# main.net
KiCad netlist of a schematic drawn in Altium Designer
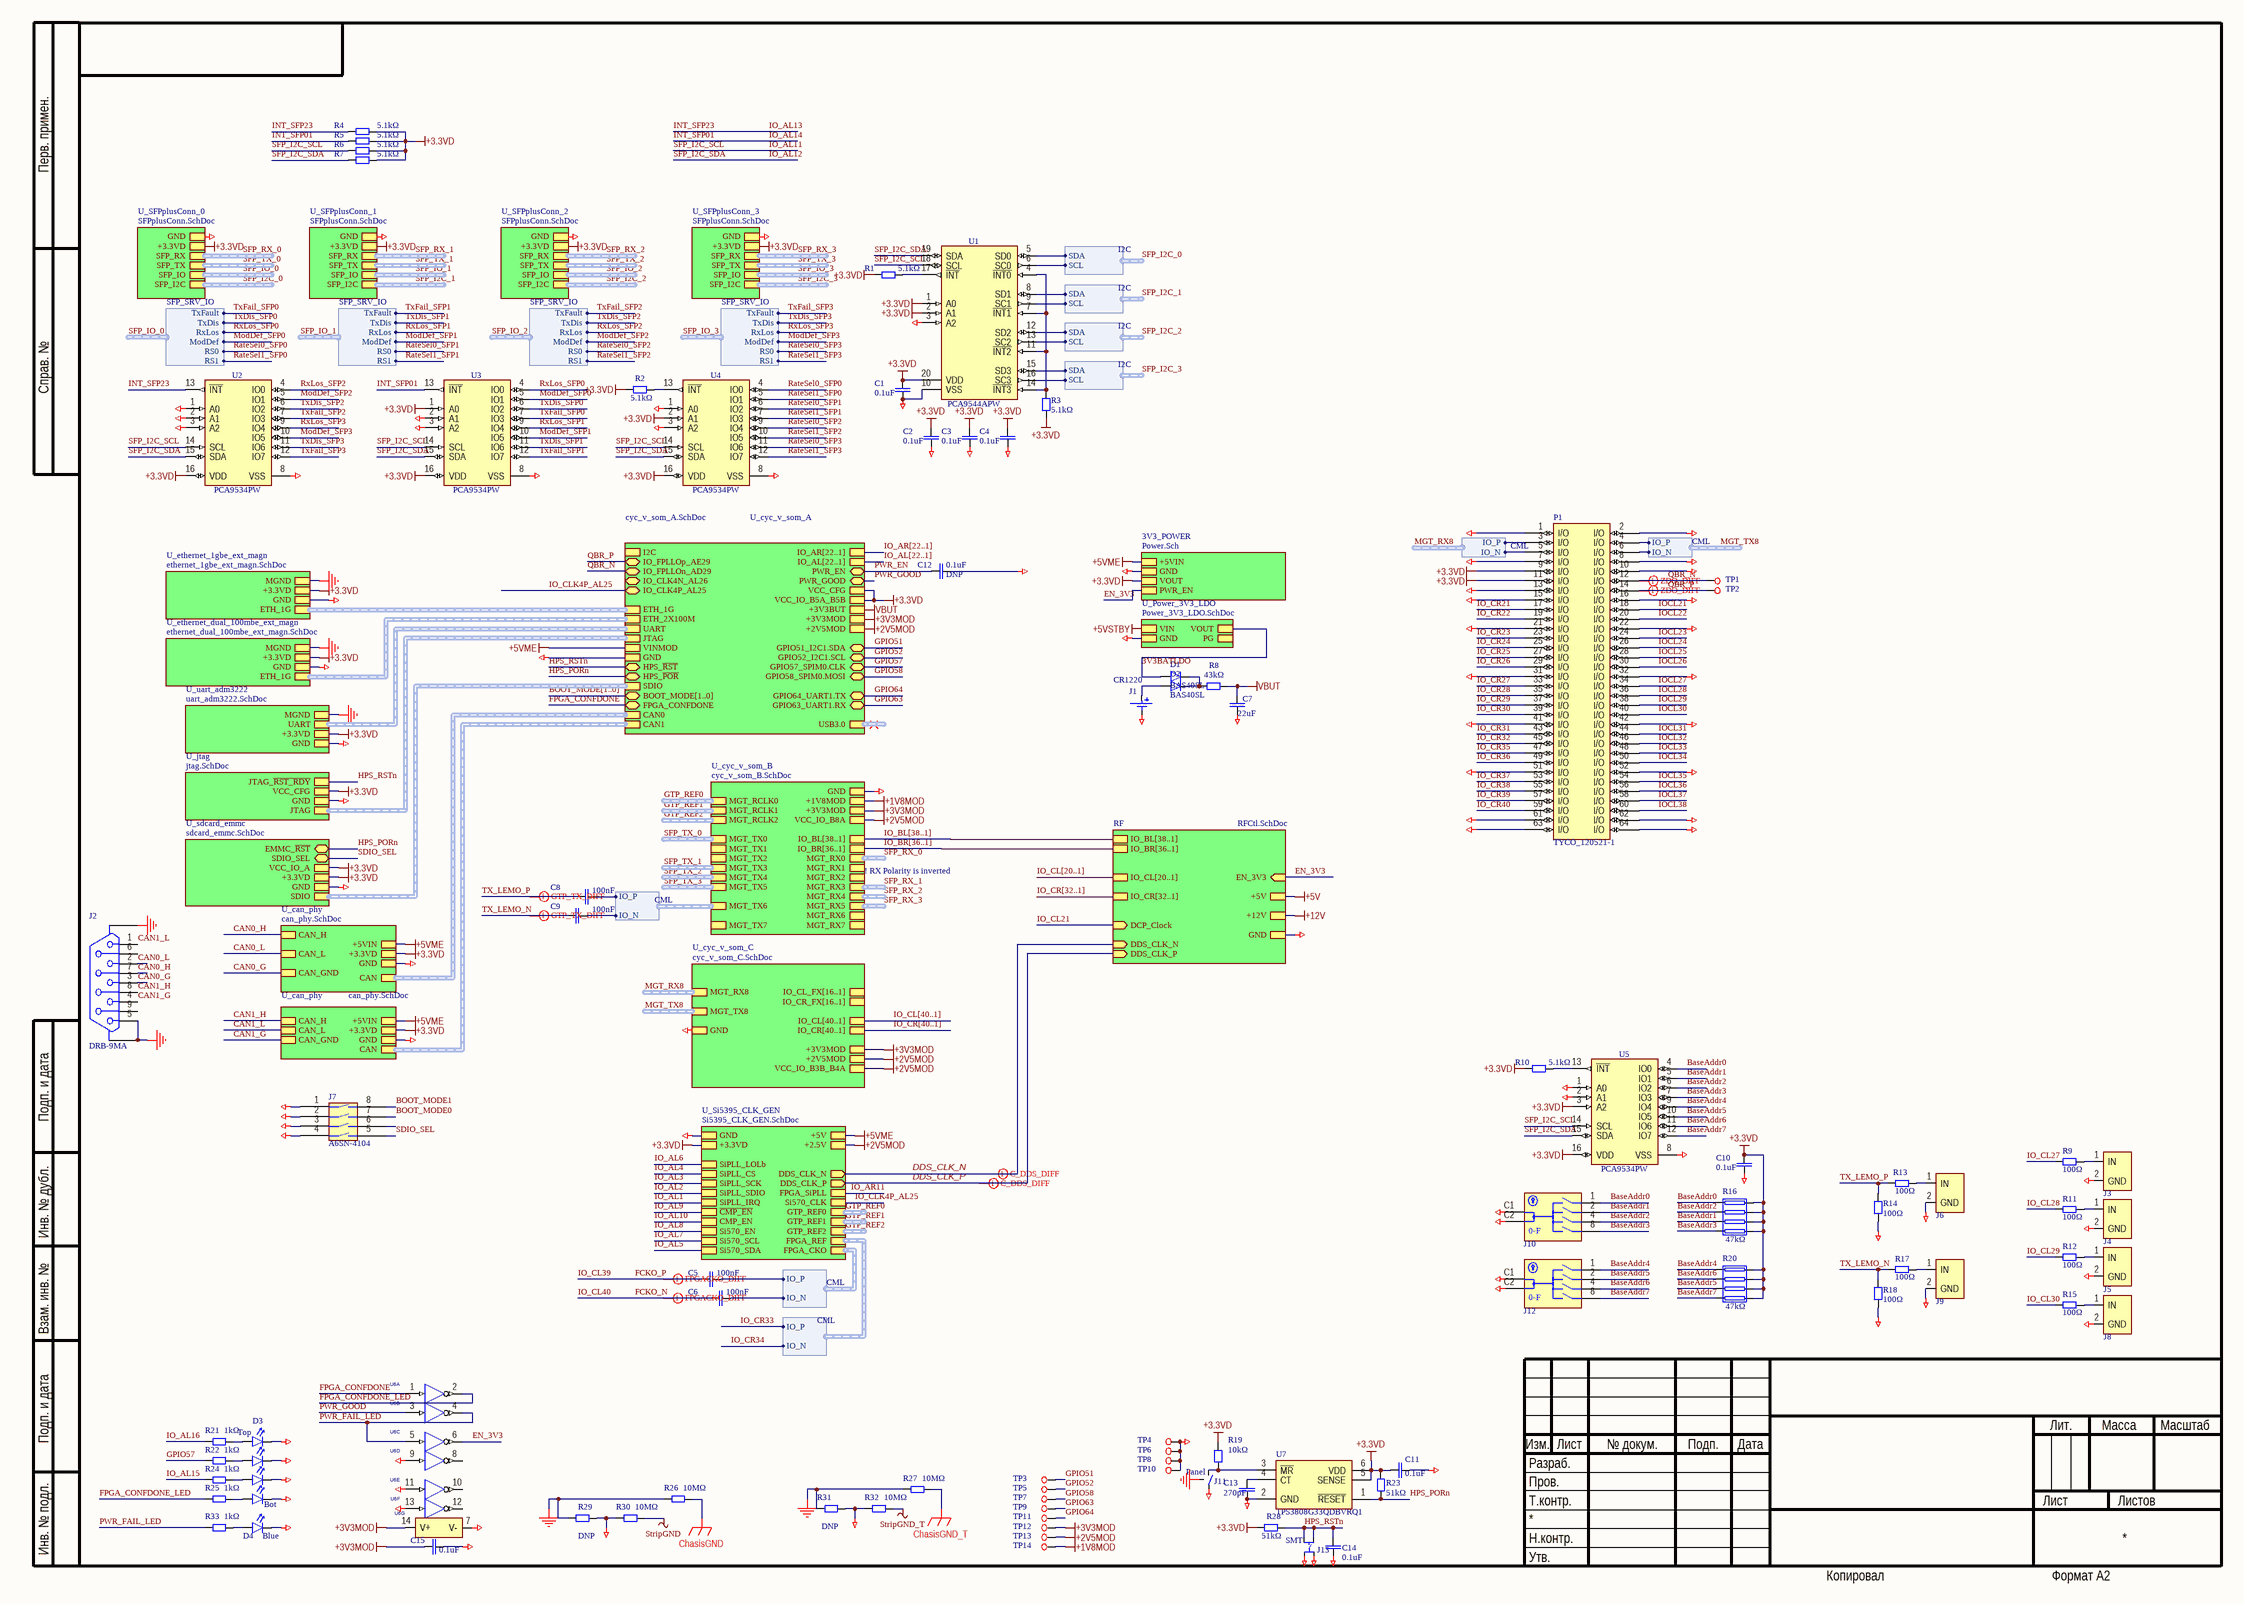
[diagram p0: main.SchDoc]

(export (version "E")
  (design (tool "Eeschema 10.0.6"))
  (components
    (comp (ref "C1")
      (value "0.1uF")
      (footprint "CAPC2012N")
      (description "Generic ceramic SMD capacitor")
      (fields (field (name "MAINTAINER") "Evgeniy Kotov"))
      (libsource (lib "[Capacitors] Capacitors SMD") (part "CAPC"))
    )
    (comp (ref "C2")
      (value "0.1uF")
      (footprint "CAPC2012N")
      (description "Generic ceramic SMD capacitor")
      (fields (field (name "MAINTAINER") "Evgeniy Kotov"))
      (libsource (lib "[Capacitors] Capacitors SMD") (part "CAPC"))
    )
    (comp (ref "C3")
      (value "0.1uF")
      (footprint "CAPC2012N")
      (description "Generic ceramic SMD capacitor")
      (fields (field (name "MAINTAINER") "Evgeniy Kotov"))
      (libsource (lib "[Capacitors] Capacitors SMD") (part "CAPC"))
    )
    (comp (ref "C4")
      (value "0.1uF")
      (footprint "CAPC2012N")
      (description "Generic ceramic SMD capacitor")
      (fields (field (name "MAINTAINER") "Evgeniy Kotov"))
      (libsource (lib "[Capacitors] Capacitors SMD") (part "CAPC"))
    )
    (comp (ref "C5")
      (value "100nF")
      (footprint "CAPC1608N")
      (description "Generic ceramic SMD capacitor")
      (fields (field (name "MAINTAINER") "Evgeniy Kotov"))
      (libsource (lib "carrier") (part "CAPC"))
    )
    (comp (ref "C6")
      (value "100nF")
      (footprint "CAPC1608N")
      (description "Generic ceramic SMD capacitor")
      (fields (field (name "MAINTAINER") "Evgeniy Kotov"))
      (libsource (lib "carrier") (part "CAPC"))
    )
    (comp (ref "C7")
      (value "22uF")
      (footprint "CAPC2012N")
      (description "Generic ceramic SMD capacitor")
      (fields (field (name "MAINTAINER") "Evgeniy Kotov"))
      (libsource (lib "carrier") (part "CAPC"))
    )
    (comp (ref "C8")
      (value "100nF")
      (footprint "CAPC1608N")
      (description "Generic ceramic SMD capacitor")
      (fields (field (name "MAINTAINER") "Evgeniy Kotov"))
      (libsource (lib "carrier") (part "CAPC"))
    )
    (comp (ref "C9")
      (value "100nF")
      (footprint "CAPC1608N")
      (description "Generic ceramic SMD capacitor")
      (fields (field (name "MAINTAINER") "Evgeniy Kotov"))
      (libsource (lib "carrier") (part "CAPC"))
    )
    (comp (ref "C10")
      (value "0.1uF")
      (footprint "CAPC2012N")
      (description "Generic ceramic SMD capacitor")
      (fields (field (name "MAINTAINER") "Evgeniy Kotov"))
      (libsource (lib "[Capacitors] Capacitors SMD") (part "CAPC"))
    )
    (comp (ref "C11")
      (value "0.1uF")
      (footprint "CAPC2012N")
      (description "Generic ceramic SMD capacitor")
      (fields (field (name "MAINTAINER") "Evgeniy Kotov"))
      (libsource (lib "[Capacitors] Capacitors SMD") (part "CAPC"))
    )
    (comp (ref "C12")
      (value "DNP")
      (footprint "CAPC2012N")
      (description "Generic ceramic SMD capacitor")
      (fields (field (name "PARTFIELD") "0.1uF") (field (name "MAINTAINER") "Evgeniy Kotov"))
      (libsource (lib "[Capacitors] Capacitors SMD") (part "CAPC"))
    )
    (comp (ref "C13")
      (value "270pF")
      (footprint "CAPC2012N")
      (description "Generic ceramic SMD capacitor")
      (fields (field (name "MAINTAINER") "Evgeniy Kotov"))
      (libsource (lib "[Capacitors] Capacitors SMD") (part "CAPC"))
    )
    (comp (ref "C14")
      (value "0.1uF")
      (footprint "CAPC2012N")
      (description "Generic ceramic SMD capacitor")
      (fields (field (name "MAINTAINER") "Evgeniy Kotov"))
      (libsource (lib "[Capacitors] Capacitors SMD") (part "CAPC"))
    )
    (comp (ref "C15")
      (value "0.1uF")
      (footprint "CAPC2012N")
      (description "Generic ceramic SMD capacitor")
      (fields (field (name "MAINTAINER") "Evgeniy Kotov"))
      (libsource (lib "[Capacitors] Capacitors SMD") (part "CAPC"))
    )
    (comp (ref "D1")
      (value "BAS40SL")
      (footprint "SOD_923")
      (description "Schottky Barrier Diode")
      (fields (field (name "MAINTAINER") "Evgeniy Kotov"))
      (libsource (lib "vme6U_carrier_Cyc_V_SoC") (part "BAS40SL"))
    )
    (comp (ref "D2")
      (value "BAS40SL")
      (footprint "SOD_923")
      (description "Schottky Barrier Diode")
      (fields (field (name "MAINTAINER") "Evgeniy Kotov"))
      (libsource (lib "vme6U_carrier_Cyc_V_SoC") (part "BAS40SL"))
    )
    (comp (ref "D3")
      (value "H485CGDL")
      (footprint "LED_H485C")
      (fields (field (name "MAINTAINER") "Evgeniy Kotov"))
      (libsource (lib "[ICs And Semiconductors] Diodes") (part "LEDx4_H485CGDL"))
    )
    (comp (ref "D4")
      (value "LB Q39E-N1OO-35-1")
      (footprint "LEDC1608N")
      (description "SMD Led, 0603")
      (fields (field (name "COLOR") "Blue") (field (name "MAINTAINER") "Evgeniy Kotov"))
      (libsource (lib "[ICs And Semiconductors] Diodes") (part "LED_SMD0603"))
    )
    (comp (ref "J1")
      (value "BC501SM")
      (footprint "BAT_CR1220")
      (description "BATTERY HOLDER COIN 12.5MM SMD")
      (fields (field (name "MAINTAINER") "Evgeniy Kotov"))
      (libsource (lib "[Connectors] Miscellaneous") (part "BAT_CR1220"))
    )
    (comp (ref "J2")
      (value "DRB-9MA")
      (footprint "DRB-9MA")
      (description "D-SUB; 9-pin, male, flange 7.2mm")
      (libsource (lib "[Connectors] Miscellaneous") (part "DRB-9MA"))
    )
    (comp (ref "J3")
      (value "DNP")
      (footprint "LEMO_EPA.00.250.NTN")
      (libsource (lib "carrier") (part "LEMO_EPA.00.250"))
    )
    (comp (ref "J4")
      (value "DNP")
      (footprint "LEMO_EPA.00.250.NTN")
      (libsource (lib "carrier") (part "LEMO_EPA.00.250"))
    )
    (comp (ref "J5")
      (value "DNP")
      (footprint "LEMO_EPA.00.250.NTN")
      (libsource (lib "carrier") (part "LEMO_EPA.00.250"))
    )
    (comp (ref "J6")
      (value "DNP")
      (footprint "LEMO_EPA.00.250.NTN")
      (libsource (lib "carrier") (part "LEMO_EPA.00.250"))
    )
    (comp (ref "J7")
      (value "A6SN-4104")
      (footprint "DIPSW4-A6SN8")
      (description "SMD DIP Switch, Omron A6H or A6SN series")
      (fields (field (name "MANUFACTURER") "Omron"))
      (libsource (lib "[Connectors] Miscellaneous") (part "DIPSW4"))
    )
    (comp (ref "J8")
      (value "DNP")
      (footprint "LEMO_EPA.00.250.NTN")
      (libsource (lib "carrier") (part "LEMO_EPA.00.250"))
    )
    (comp (ref "J9")
      (value "DNP")
      (footprint "LEMO_EPA.00.250.NTN")
      (libsource (lib "carrier") (part "LEMO_EPA.00.250"))
    )
    (comp (ref "J10")
      (value "ERD116XSZ")
      (footprint "SW_ECE_ERD116XSZ")
      (libsource (lib "[Connectors] Miscellaneous") (part "ERD116XSZ"))
    )
    (comp (ref "J11")
      (value "PTS645VL582LFS")
      (footprint "PTS645VL582LFS")
      (description "Tactile Switch SPST-NO Side Actuated Through Hole, Right Angle")
      (fields (field (name "MAINTAINER") "Evgeniy Kotov"))
      (libsource (lib "[Connectors] Miscellaneous") (part "PTS645VL582LFS"))
    )
    (comp (ref "J12")
      (value "ERD116XSZ")
      (footprint "SW_ECE_ERD116XSZ")
      (libsource (lib "[Connectors] Miscellaneous") (part "ERD116XSZ"))
    )
    (comp (ref "J13")
      (value "PTS645SL43SMTR92")
      (footprint "PTS645SL43SMTR92")
      (description "Tactile Switch SPST-NO Top Actuated Surface Mount")
      (fields (field (name "MAINTAINER") "Evgeniy Kotov"))
      (libsource (lib "[Connectors] Miscellaneous") (part "PTS645SL43SMTR92"))
    )
    (comp (ref "P1")
      (value "TYCO_120521-1")
      (footprint "TYCO_120521-1")
      (description "PCI Mezzanine Connector; IEEE 1386")
      (fields (field (name "MANUFACTURER") "TE Connectivity"))
      (libsource (lib "[Connectors] Miscellaneous") (part "PCI_PMC_TYCO_120521-1"))
    )
    (comp (ref "R1")
      (value "5.1kΩ")
      (footprint "RESC2012N")
      (description "Resistor, Generic, SMD")
      (fields (field (name "MAINTAINER") "Evgeniy Kotov"))
      (libsource (lib "carrier") (part "RESC"))
    )
    (comp (ref "R2")
      (value "5.1kΩ")
      (footprint "RESC2012N")
      (description "Resistor, Generic, SMD")
      (fields (field (name "MAINTAINER") "Evgeniy Kotov"))
      (libsource (lib "carrier") (part "RESC"))
    )
    (comp (ref "R3")
      (value "5.1kΩ")
      (footprint "RESC2012N")
      (description "Resistor, Generic, SMD")
      (fields (field (name "MAINTAINER") "Evgeniy Kotov"))
      (libsource (lib "[Resistors] Resistors SMD") (part "RESC"))
    )
    (comp (ref "R4")
      (value "5.1kΩ")
      (footprint "RESC2012N")
      (description "Resistor, Generic, SMD")
      (fields (field (name "MAINTAINER") "Evgeniy Kotov"))
      (libsource (lib "[Resistors] Resistors SMD") (part "RESC"))
    )
    (comp (ref "R5")
      (value "5.1kΩ")
      (footprint "RESC2012N")
      (description "Resistor, Generic, SMD")
      (fields (field (name "MAINTAINER") "Evgeniy Kotov"))
      (libsource (lib "[Resistors] Resistors SMD") (part "RESC"))
    )
    (comp (ref "R6")
      (value "5.1kΩ")
      (footprint "RESC2012N")
      (description "Resistor, Generic, SMD")
      (fields (field (name "MAINTAINER") "Evgeniy Kotov"))
      (libsource (lib "[Resistors] Resistors SMD") (part "RESC"))
    )
    (comp (ref "R7")
      (value "5.1kΩ")
      (footprint "RESC2012N")
      (description "Resistor, Generic, SMD")
      (fields (field (name "MAINTAINER") "Evgeniy Kotov"))
      (libsource (lib "[Resistors] Resistors SMD") (part "RESC"))
    )
    (comp (ref "R8")
      (value "43kΩ")
      (footprint "RESC2012N")
      (description "Resistor, Generic, SMD")
      (fields (field (name "MAINTAINER") "Evgeniy Kotov"))
      (libsource (lib "[Resistors] Resistors SMD") (part "RESC"))
    )
    (comp (ref "R9")
      (value "100Ω")
      (footprint "RESC1608N")
      (description "Resistor, Generic, SMD")
      (fields (field (name "MAINTAINER") "Evgeniy Kotov"))
      (libsource (lib "carrier") (part "RESC"))
    )
    (comp (ref "R10")
      (value "5.1kΩ")
      (footprint "RESC2012N")
      (description "Resistor, Generic, SMD")
      (fields (field (name "MAINTAINER") "Evgeniy Kotov"))
      (libsource (lib "carrier") (part "RESC"))
    )
    (comp (ref "R11")
      (value "100Ω")
      (footprint "RESC1608N")
      (description "Resistor, Generic, SMD")
      (fields (field (name "MAINTAINER") "Evgeniy Kotov"))
      (libsource (lib "carrier") (part "RESC"))
    )
    (comp (ref "R12")
      (value "100Ω")
      (footprint "RESC1608N")
      (description "Resistor, Generic, SMD")
      (fields (field (name "MAINTAINER") "Evgeniy Kotov"))
      (libsource (lib "carrier") (part "RESC"))
    )
    (comp (ref "R13")
      (value "100Ω")
      (footprint "RESC1608N")
      (description "Resistor, Generic, SMD")
      (fields (field (name "MAINTAINER") "Evgeniy Kotov"))
      (libsource (lib "carrier") (part "RESC"))
    )
    (comp (ref "R14")
      (value "100Ω")
      (footprint "RESC1608N")
      (description "Resistor, Generic, SMD")
      (fields (field (name "MAINTAINER") "Evgeniy Kotov"))
      (libsource (lib "carrier") (part "RESC"))
    )
    (comp (ref "R15")
      (value "100Ω")
      (footprint "RESC1608N")
      (description "Resistor, Generic, SMD")
      (fields (field (name "MAINTAINER") "Evgeniy Kotov"))
      (libsource (lib "carrier") (part "RESC"))
    )
    (comp (ref "R16")
      (value "47kΩ")
      (footprint "CAY16-J4")
      (fields (field (name "Comment") "CAY16-4702F4LF") (field (name "MAINTAINER") "Anton Pavlenko"))
      (libsource (lib "[Resistors] Resistors SMD") (part "RESPACK4"))
    )
    (comp (ref "R17")
      (value "100Ω")
      (footprint "RESC1608N")
      (description "Resistor, Generic, SMD")
      (fields (field (name "MAINTAINER") "Evgeniy Kotov"))
      (libsource (lib "carrier") (part "RESC"))
    )
    (comp (ref "R18")
      (value "100Ω")
      (footprint "RESC1608N")
      (description "Resistor, Generic, SMD")
      (fields (field (name "MAINTAINER") "Evgeniy Kotov"))
      (libsource (lib "carrier") (part "RESC"))
    )
    (comp (ref "R19")
      (value "10kΩ")
      (footprint "RESC2012N")
      (description "Resistor, Generic, SMD")
      (fields (field (name "MAINTAINER") "Evgeniy Kotov"))
      (libsource (lib "carrier") (part "RESC"))
    )
    (comp (ref "R20")
      (value "47kΩ")
      (footprint "CAY16-J4")
      (fields (field (name "Comment") "CAY16-4702F4LF") (field (name "MAINTAINER") "Anton Pavlenko"))
      (libsource (lib "[Resistors] Resistors SMD") (part "RESPACK4"))
    )
    (comp (ref "R21")
      (value "1kΩ")
      (footprint "RESC2012N")
      (description "Resistor, Generic, SMD")
      (fields (field (name "MAINTAINER") "Evgeniy Kotov"))
      (libsource (lib "[Resistors] Resistors SMD") (part "RESC"))
    )
    (comp (ref "R22")
      (value "1kΩ")
      (footprint "RESC2012N")
      (description "Resistor, Generic, SMD")
      (fields (field (name "MAINTAINER") "Evgeniy Kotov"))
      (libsource (lib "[Resistors] Resistors SMD") (part "RESC"))
    )
    (comp (ref "R23")
      (value "51kΩ")
      (footprint "RESC2012N")
      (description "Resistor, Generic, SMD")
      (fields (field (name "MAINTAINER") "Evgeniy Kotov"))
      (libsource (lib "carrier") (part "RESC"))
    )
    (comp (ref "R24")
      (value "1kΩ")
      (footprint "RESC2012N")
      (description "Resistor, Generic, SMD")
      (fields (field (name "MAINTAINER") "Evgeniy Kotov"))
      (libsource (lib "[Resistors] Resistors SMD") (part "RESC"))
    )
    (comp (ref "R25")
      (value "1kΩ")
      (footprint "RESC2012N")
      (description "Resistor, Generic, SMD")
      (fields (field (name "MAINTAINER") "Evgeniy Kotov"))
      (libsource (lib "[Resistors] Resistors SMD") (part "RESC"))
    )
    (comp (ref "R26")
      (value "10MΩ")
      (footprint "RESC2012N")
      (description "Resistor, Generic, SMD")
      (fields (field (name "MAINTAINER") "Evgeniy Kotov"))
      (libsource (lib "[Resistors] Resistors SMD") (part "RESC"))
    )
    (comp (ref "R27")
      (value "10MΩ")
      (footprint "RESC2012N")
      (description "Resistor, Generic, SMD")
      (fields (field (name "MAINTAINER") "Evgeniy Kotov"))
      (libsource (lib "[Resistors] Resistors SMD") (part "RESC"))
    )
    (comp (ref "R28")
      (value "51kΩ")
      (footprint "RESC2012N")
      (description "Resistor, Generic, SMD")
      (fields (field (name "MAINTAINER") "Evgeniy Kotov"))
      (libsource (lib "carrier") (part "RESC"))
    )
    (comp (ref "R29")
      (value "DNP")
      (footprint "RESC2012N")
      (description "Resistor, Generic, SMD")
      (fields (field (name "MAINTAINER") "Evgeniy Kotov"))
      (libsource (lib "[Resistors] Resistors SMD") (part "RESC"))
    )
    (comp (ref "R30")
      (value "10MΩ")
      (footprint "RESC2012N")
      (description "Resistor, Generic, SMD")
      (fields (field (name "MAINTAINER") "Evgeniy Kotov"))
      (libsource (lib "[Resistors] Resistors SMD") (part "RESC"))
    )
    (comp (ref "R31")
      (value "DNP")
      (footprint "RESC2012N")
      (description "Resistor, Generic, SMD")
      (fields (field (name "MAINTAINER") "Evgeniy Kotov"))
      (libsource (lib "[Resistors] Resistors SMD") (part "RESC"))
    )
    (comp (ref "R32")
      (value "10MΩ")
      (footprint "RESC2012N")
      (description "Resistor, Generic, SMD")
      (fields (field (name "MAINTAINER") "Evgeniy Kotov"))
      (libsource (lib "[Resistors] Resistors SMD") (part "RESC"))
    )
    (comp (ref "R33")
      (value "1kΩ")
      (footprint "RESC2012N")
      (description "Resistor, Generic, SMD")
      (fields (field (name "MAINTAINER") "Evgeniy Kotov"))
      (libsource (lib "[Resistors] Resistors SMD") (part "RESC"))
    )
    (comp (ref "TP1")
      (value "test point")
      (footprint "TEST_POINT")
      (description "testPoint")
      (libsource (lib "carrier") (part "TestPoint"))
    )
    (comp (ref "TP2")
      (value "test point")
      (footprint "TEST_POINT")
      (description "testPoint")
      (libsource (lib "carrier") (part "TestPoint"))
    )
    (comp (ref "TP3")
      (value "test point")
      (footprint "TEST_POINT")
      (description "testPoint")
      (libsource (lib "carrier") (part "TestPoint"))
    )
    (comp (ref "TP4")
      (value "test point")
      (footprint "TEST_POINT")
      (description "testPoint")
      (libsource (lib "carrier") (part "TestPoint"))
    )
    (comp (ref "TP5")
      (value "test point")
      (footprint "TEST_POINT")
      (description "testPoint")
      (libsource (lib "carrier") (part "TestPoint"))
    )
    (comp (ref "TP6")
      (value "test point")
      (footprint "TEST_POINT")
      (description "testPoint")
      (libsource (lib "carrier") (part "TestPoint"))
    )
    (comp (ref "TP7")
      (value "test point")
      (footprint "TEST_POINT")
      (description "testPoint")
      (libsource (lib "carrier") (part "TestPoint"))
    )
    (comp (ref "TP8")
      (value "test point")
      (footprint "TEST_POINT")
      (description "testPoint")
      (libsource (lib "carrier") (part "TestPoint"))
    )
    (comp (ref "TP9")
      (value "test point")
      (footprint "TEST_POINT")
      (description "testPoint")
      (libsource (lib "carrier") (part "TestPoint"))
    )
    (comp (ref "TP10")
      (value "test point")
      (footprint "TEST_POINT")
      (description "testPoint")
      (libsource (lib "carrier") (part "TestPoint"))
    )
    (comp (ref "TP11")
      (value "test point")
      (footprint "TEST_POINT")
      (description "testPoint")
      (libsource (lib "carrier") (part "TestPoint"))
    )
    (comp (ref "TP12")
      (value "test point")
      (footprint "TEST_POINT")
      (description "testPoint")
      (libsource (lib "carrier") (part "TestPoint"))
    )
    (comp (ref "TP13")
      (value "test point")
      (footprint "TEST_POINT")
      (description "testPoint")
      (libsource (lib "carrier") (part "TestPoint"))
    )
    (comp (ref "TP14")
      (value "test point")
      (footprint "TEST_POINT")
      (description "testPoint")
      (libsource (lib "carrier") (part "TestPoint"))
    )
    (comp (ref "U1")
      (value "PCA9544APW")
      (footprint "SOP65P640X110-20N")
      (description "4-Channel I2C-Bus Multiplexer with Interrupt Logic")
      (fields (field (name "MANUFACTURER") "NXP SEMICONDUCTORS") (field (name "AUTHOR") "CERN DEM JLC"))
      (libsource (lib "Analog & Interface") (part "PCA9544APW"))
    )
    (comp (ref "U2")
      (value "PCA9534PW")
      (footprint "SOP65P640X110-16N")
      (description "8-Bit I2C-Bus and SMBus Low Power I/O Port with Interrupt")
      (fields (field (name "MANUFACTURER") "ANALOG DEVICES") (field (name "AUTHOR") "CERN DEM JLC"))
      (libsource (lib "Analog & Interface") (part "PCA9534PW"))
    )
    (comp (ref "U3")
      (value "PCA9534PW")
      (footprint "SOP65P640X110-16N")
      (description "8-Bit I2C-Bus and SMBus Low Power I/O Port with Interrupt")
      (fields (field (name "MANUFACTURER") "ANALOG DEVICES") (field (name "AUTHOR") "CERN DEM JLC"))
      (libsource (lib "Analog & Interface") (part "PCA9534PW"))
    )
    (comp (ref "U4")
      (value "PCA9534PW")
      (footprint "SOP65P640X110-16N")
      (description "8-Bit I2C-Bus and SMBus Low Power I/O Port with Interrupt")
      (fields (field (name "MANUFACTURER") "ANALOG DEVICES") (field (name "AUTHOR") "CERN DEM JLC"))
      (libsource (lib "Analog & Interface") (part "PCA9534PW"))
    )
    (comp (ref "U5")
      (value "PCA9534PW")
      (footprint "SOP65P640X110-16N")
      (description "8-Bit I2C-Bus and SMBus Low Power I/O Port with Interrupt")
      (fields (field (name "MANUFACTURER") "ANALOG DEVICES") (field (name "AUTHOR") "CERN DEM JLC"))
      (libsource (lib "Analog & Interface") (part "PCA9534PW"))
    )
    (comp (ref "U6")
      (value "SN74LVC04APW")
      (footprint "SOP65P640X110-14N")
      (description "Sextuple NOR Gate")
      (fields (field (name "MANUFACTURER") "Texas Instruments"))
      (libsource (lib "[ICs And Semiconductors] Analog & Interface") (part "SN74LVC04APW"))
    )
    (comp (ref "U7")
      (value "TPS3808G33QDBVRQ1")
      (footprint "SOT95P280X100-6N")
      (description "Low-Quiescent-Current Programmable-Delay Supervisory Circuit")
      (fields (field (name "MAINTAINER") "Evgeniy Kotov"))
      (libsource (lib "[ICs And Semiconductors] Analog & Interface") (part "TPS3808G33QDBVRQ1"))
    )
  )
  (nets
    (net (code "187") (name "+1V8MOD") (class "Default") (node (ref "TP14") (pin "1") (pintype "passive")))
    (net (code "188") (name "+2V5MOD") (class "Default") (node (ref "TP13") (pin "1") (pintype "passive")))
    (net (code "189") (name "+3.3VD") (class "Default")
      (node (ref "C1") (pin "1") (pintype "passive"))
      (node (ref "C10") (pin "1") (pintype "passive"))
      (node (ref "C11") (pin "2") (pintype "passive"))
      (node (ref "C2") (pin "1") (pintype "passive"))
      (node (ref "C3") (pin "1") (pintype "passive"))
      (node (ref "C4") (pin "1") (pintype "passive"))
      (node (ref "P1") (pin "11") (pinfunction "I/O_11") (pintype "bidirectional"))
      (node (ref "P1") (pin "9") (pinfunction "I/O_9") (pintype "bidirectional"))
      (node (ref "R1") (pin "1") (pintype "passive"))
      (node (ref "R10") (pin "1") (pintype "passive"))
      (node (ref "R16") (pin "5") (pinfunction "5_5") (pintype "passive"))
      (node (ref "R16") (pin "6") (pinfunction "6_6") (pintype "passive"))
      (node (ref "R16") (pin "7") (pinfunction "7_7") (pintype "passive"))
      (node (ref "R16") (pin "8") (pinfunction "8_8") (pintype "passive"))
      (node (ref "R19") (pin "1") (pintype "passive"))
      (node (ref "R2") (pin "1") (pintype "passive"))
      (node (ref "R20") (pin "5") (pinfunction "5_5") (pintype "passive"))
      (node (ref "R20") (pin "6") (pinfunction "6_6") (pintype "passive"))
      (node (ref "R20") (pin "7") (pinfunction "7_7") (pintype "passive"))
      (node (ref "R20") (pin "8") (pinfunction "8_8") (pintype "passive"))
      (node (ref "R23") (pin "1") (pintype "passive"))
      (node (ref "R28") (pin "1") (pintype "passive"))
      (node (ref "R3") (pin "2") (pintype "passive"))
      (node (ref "R4") (pin "2") (pintype "passive"))
      (node (ref "R5") (pin "2") (pintype "passive"))
      (node (ref "R6") (pin "2") (pintype "passive"))
      (node (ref "R7") (pin "2") (pintype "passive"))
      (node (ref "U1") (pin "1") (pinfunction "A0_1") (pintype "input"))
      (node (ref "U1") (pin "2") (pinfunction "A1_2") (pintype "input"))
      (node (ref "U1") (pin "20") (pinfunction "VDD_20") (pintype "power_in"))
      (node (ref "U2") (pin "16") (pinfunction "VDD_16") (pintype "bidirectional"))
      (node (ref "U3") (pin "1") (pinfunction "A0_1") (pintype "input"))
      (node (ref "U3") (pin "16") (pinfunction "VDD_16") (pintype "bidirectional"))
      (node (ref "U4") (pin "16") (pinfunction "VDD_16") (pintype "bidirectional"))
      (node (ref "U4") (pin "2") (pinfunction "A1_2") (pintype "input"))
      (node (ref "U5") (pin "16") (pinfunction "VDD_16") (pintype "bidirectional"))
      (node (ref "U5") (pin "3") (pinfunction "A2_3") (pintype "input"))
      (node (ref "U7") (pin "5") (pinfunction "SENSE_5") (pintype "passive"))
      (node (ref "U7") (pin "6") (pinfunction "VDD_6") (pintype "passive"))
    )
    (net (code "190") (name "+3V3MOD") (class "Default")
      (node (ref "C15") (pin "2") (pintype "passive"))
      (node (ref "TP12") (pin "1") (pintype "passive"))
      (node (ref "U6") (pin "14") (pinfunction "V+_14") (pintype "passive"))
    )
    (net (code "195") (name "/3V3BATLDO") (class "Default")
      (node (ref "D1") (pin "1") (pinfunction "A_1") (pintype "passive"))
    )
    (net (code "196") (name "/BOOT_MODE0") (class "Default")
      (node (ref "J7") (pin "7") (pinfunction "7_7") (pintype "passive"))
    )
    (net (code "197") (name "/BOOT_MODE1") (class "Default")
      (node (ref "J7") (pin "8") (pinfunction "8_8") (pintype "passive"))
    )
    (net (code "199") (name "/BaseAddr0") (class "Default")
      (node (ref "J10") (pin "1") (pinfunction "1_1") (pintype "passive"))
      (node (ref "R16") (pin "4") (pinfunction "4_4") (pintype "passive"))
      (node (ref "U5") (pin "4") (pinfunction "IO0_4") (pintype "bidirectional"))
    )
    (net (code "200") (name "/BaseAddr1") (class "Default")
      (node (ref "J10") (pin "2") (pinfunction "2_2") (pintype "passive"))
      (node (ref "R16") (pin "2") (pinfunction "2_2") (pintype "passive"))
      (node (ref "U5") (pin "5") (pinfunction "IO1_5") (pintype "bidirectional"))
    )
    (net (code "201") (name "/BaseAddr2") (class "Default")
      (node (ref "J10") (pin "4") (pinfunction "4_4") (pintype "passive"))
      (node (ref "R16") (pin "3") (pinfunction "3_3") (pintype "passive"))
      (node (ref "U5") (pin "6") (pinfunction "IO2_6") (pintype "bidirectional"))
    )
    (net (code "202") (name "/BaseAddr3") (class "Default")
      (node (ref "J10") (pin "8") (pinfunction "8_8") (pintype "passive"))
      (node (ref "R16") (pin "1") (pinfunction "1_1") (pintype "passive"))
      (node (ref "U5") (pin "7") (pinfunction "IO3_7") (pintype "bidirectional"))
    )
    (net (code "203") (name "/BaseAddr4") (class "Default")
      (node (ref "J12") (pin "1") (pinfunction "1_1") (pintype "passive"))
      (node (ref "R20") (pin "4") (pinfunction "4_4") (pintype "passive"))
      (node (ref "U5") (pin "9") (pinfunction "IO4_9") (pintype "bidirectional"))
    )
    (net (code "204") (name "/BaseAddr5") (class "Default")
      (node (ref "J12") (pin "2") (pinfunction "2_2") (pintype "passive"))
      (node (ref "R20") (pin "2") (pinfunction "2_2") (pintype "passive"))
      (node (ref "U5") (pin "10") (pinfunction "IO5_10") (pintype "bidirectional"))
    )
    (net (code "205") (name "/BaseAddr6") (class "Default")
      (node (ref "J12") (pin "4") (pinfunction "4_4") (pintype "passive"))
      (node (ref "R20") (pin "3") (pinfunction "3_3") (pintype "passive"))
      (node (ref "U5") (pin "11") (pinfunction "IO6_11") (pintype "bidirectional"))
    )
    (net (code "206") (name "/BaseAddr7") (class "Default")
      (node (ref "J12") (pin "8") (pinfunction "8_8") (pintype "passive"))
      (node (ref "R20") (pin "1") (pinfunction "1_1") (pintype "passive"))
      (node (ref "U5") (pin "12") (pinfunction "IO7_12") (pintype "bidirectional"))
    )
    (net (code "207") (name "/CAN0_G") (class "Default")
      (node (ref "J2") (pin "3") (pinfunction "3_3") (pintype "passive"))
    )
    (net (code "208") (name "/CAN0_H") (class "Default")
      (node (ref "J2") (pin "7") (pinfunction "7_7") (pintype "passive"))
    )
    (net (code "209") (name "/CAN0_L") (class "Default")
      (node (ref "J2") (pin "2") (pinfunction "2_2") (pintype "passive"))
    )
    (net (code "211") (name "/CAN1_G") (class "Default")
      (node (ref "J2") (pin "4") (pinfunction "4_4") (pintype "passive"))
    )
    (net (code "212") (name "/CAN1_H") (class "Default")
      (node (ref "J2") (pin "8") (pinfunction "8_8") (pintype "passive"))
    )
    (net (code "213") (name "/CAN1_L") (class "Default")
      (node (ref "J2") (pin "1") (pinfunction "1_1") (pintype "passive"))
    )
    (net (code "217") (name "/EN_3V3") (class "Default")
      (node (ref "U6") (pin "6") (pinfunction "B_6") (pintype "output"))
    )
    (net (code "220") (name "/FPGA_CONFDONE") (class "Default")
      (node (ref "U6") (pin "1") (pinfunction "A_1") (pintype "input"))
    )
    (net (code "221") (name "/FPGA_CONFDONE_LED") (class "Default")
      (node (ref "R25") (pin "1") (pintype "passive"))
      (node (ref "U6") (pin "2") (pinfunction "B_2") (pintype "output"))
    )
    (net (code "222") (name "/GPIO51") (class "Default") (node (ref "TP3") (pin "1") (pintype "passive")))
    (net (code "223") (name "/GPIO52") (class "Default") (node (ref "TP5") (pin "1") (pintype "passive")))
    (net (code "224") (name "/GPIO57") (class "Default") (node (ref "R22") (pin "1") (pintype "passive")))
    (net (code "225") (name "/GPIO58") (class "Default") (node (ref "TP7") (pin "1") (pintype "passive")))
    (net (code "226") (name "/GPIO63") (class "Default") (node (ref "TP9") (pin "1") (pintype "passive")))
    (net (code "227") (name "/GPIO64") (class "Default") (node (ref "TP11") (pin "1") (pintype "passive")))
    (net (code "228") (name "/HPS_PORn") (class "Default")
      (node (ref "R23") (pin "2") (pintype "passive"))
      (node (ref "U7") (pin "1") (pinfunction "~{RESET}_1") (pintype "passive"))
    )
    (net (code "229") (name "/HPS_RSTn") (class "Default")
      (node (ref "C14") (pin "1") (pintype "passive"))
      (node (ref "J13") (pin "1") (pintype "passive"))
      (node (ref "J13") (pin "2") (pintype "passive"))
      (node (ref "R28") (pin "2") (pintype "passive"))
    )
    (net (code "231") (name "/IOCL21") (class "Default")
      (node (ref "P1") (pin "18") (pinfunction "I/O_18") (pintype "bidirectional"))
    )
    (net (code "232") (name "/IOCL22") (class "Default")
      (node (ref "P1") (pin "20") (pinfunction "I/O_20") (pintype "bidirectional"))
    )
    (net (code "233") (name "/IOCL23") (class "Default")
      (node (ref "P1") (pin "24") (pinfunction "I/O_24") (pintype "bidirectional"))
    )
    (net (code "234") (name "/IOCL24") (class "Default")
      (node (ref "P1") (pin "26") (pinfunction "I/O_26") (pintype "bidirectional"))
    )
    (net (code "235") (name "/IOCL25") (class "Default")
      (node (ref "P1") (pin "28") (pinfunction "I/O_28") (pintype "bidirectional"))
    )
    (net (code "236") (name "/IOCL26") (class "Default")
      (node (ref "P1") (pin "30") (pinfunction "I/O_30") (pintype "bidirectional"))
    )
    (net (code "237") (name "/IOCL27") (class "Default")
      (node (ref "P1") (pin "34") (pinfunction "I/O_34") (pintype "bidirectional"))
    )
    (net (code "238") (name "/IOCL28") (class "Default")
      (node (ref "P1") (pin "36") (pinfunction "I/O_36") (pintype "bidirectional"))
    )
    (net (code "239") (name "/IOCL29") (class "Default")
      (node (ref "P1") (pin "38") (pinfunction "I/O_38") (pintype "bidirectional"))
    )
    (net (code "240") (name "/IOCL30") (class "Default")
      (node (ref "P1") (pin "40") (pinfunction "I/O_40") (pintype "bidirectional"))
    )
    (net (code "241") (name "/IOCL31") (class "Default")
      (node (ref "P1") (pin "44") (pinfunction "I/O_44") (pintype "bidirectional"))
    )
    (net (code "242") (name "/IOCL32") (class "Default")
      (node (ref "P1") (pin "46") (pinfunction "I/O_46") (pintype "bidirectional"))
    )
    (net (code "243") (name "/IOCL33") (class "Default")
      (node (ref "P1") (pin "48") (pinfunction "I/O_48") (pintype "bidirectional"))
    )
    (net (code "244") (name "/IOCL34") (class "Default")
      (node (ref "P1") (pin "50") (pinfunction "I/O_50") (pintype "bidirectional"))
    )
    (net (code "245") (name "/IOCL35") (class "Default")
      (node (ref "P1") (pin "54") (pinfunction "I/O_54") (pintype "bidirectional"))
    )
    (net (code "246") (name "/IOCL36") (class "Default")
      (node (ref "P1") (pin "56") (pinfunction "I/O_56") (pintype "bidirectional"))
    )
    (net (code "247") (name "/IOCL37") (class "Default")
      (node (ref "P1") (pin "58") (pinfunction "I/O_58") (pintype "bidirectional"))
    )
    (net (code "248") (name "/IOCL38") (class "Default")
      (node (ref "P1") (pin "60") (pinfunction "I/O_60") (pintype "bidirectional"))
    )
    (net (code "259") (name "/IO_AL11") (class "Default")
      (node (ref "R6") (pin "1") (pintype "passive"))
      (node (ref "U1") (pin "18") (pinfunction "SCL_18") (pintype "bidirectional"))
      (node (ref "U2") (pin "14") (pinfunction "SCL_14") (pintype "input"))
      (node (ref "U3") (pin "14") (pinfunction "SCL_14") (pintype "input"))
      (node (ref "U4") (pin "14") (pinfunction "SCL_14") (pintype "input"))
      (node (ref "U5") (pin "14") (pinfunction "SCL_14") (pintype "input"))
    )
    (net (code "260") (name "/IO_AL12") (class "Default")
      (node (ref "R7") (pin "1") (pintype "passive"))
      (node (ref "U1") (pin "19") (pinfunction "SDA_19") (pintype "bidirectional"))
      (node (ref "U2") (pin "15") (pinfunction "SDA_15") (pintype "bidirectional"))
      (node (ref "U3") (pin "15") (pinfunction "SDA_15") (pintype "bidirectional"))
      (node (ref "U4") (pin "15") (pinfunction "SDA_15") (pintype "bidirectional"))
      (node (ref "U5") (pin "15") (pinfunction "SDA_15") (pintype "bidirectional"))
    )
    (net (code "261") (name "/IO_AL13") (class "Default")
      (node (ref "R4") (pin "1") (pintype "passive"))
      (node (ref "U2") (pin "13") (pinfunction "~{INT}_13") (pintype "output"))
    )
    (net (code "262") (name "/IO_AL14") (class "Default")
      (node (ref "R5") (pin "1") (pintype "passive"))
      (node (ref "U3") (pin "13") (pinfunction "~{INT}_13") (pintype "output"))
    )
    (net (code "263") (name "/IO_AL15") (class "Default") (node (ref "R24") (pin "1") (pintype "passive")))
    (net (code "264") (name "/IO_AL16") (class "Default") (node (ref "R21") (pin "1") (pintype "passive")))
    (net (code "271") (name "/IO_CL27") (class "Default") (node (ref "R9") (pin "2") (pintype "passive")))
    (net (code "272") (name "/IO_CL28") (class "Default") (node (ref "R11") (pin "2") (pintype "passive")))
    (net (code "273") (name "/IO_CL29") (class "Default") (node (ref "R12") (pin "2") (pintype "passive")))
    (net (code "274") (name "/IO_CL30") (class "Default") (node (ref "R15") (pin "2") (pintype "passive")))
    (net (code "275") (name "/IO_CL39") (class "Default") (node (ref "C5") (pin "1") (pintype "passive")))
    (net (code "276") (name "/IO_CL40") (class "Default") (node (ref "C6") (pin "1") (pintype "passive")))
    (net (code "282") (name "/IO_CR21") (class "Default")
      (node (ref "P1") (pin "17") (pinfunction "I/O_17") (pintype "bidirectional"))
    )
    (net (code "283") (name "/IO_CR22") (class "Default")
      (node (ref "P1") (pin "19") (pinfunction "I/O_19") (pintype "bidirectional"))
    )
    (net (code "284") (name "/IO_CR23") (class "Default")
      (node (ref "P1") (pin "23") (pinfunction "I/O_23") (pintype "bidirectional"))
    )
    (net (code "285") (name "/IO_CR24") (class "Default")
      (node (ref "P1") (pin "25") (pinfunction "I/O_25") (pintype "bidirectional"))
    )
    (net (code "286") (name "/IO_CR25") (class "Default")
      (node (ref "P1") (pin "27") (pinfunction "I/O_27") (pintype "bidirectional"))
    )
    (net (code "287") (name "/IO_CR26") (class "Default")
      (node (ref "P1") (pin "29") (pinfunction "I/O_29") (pintype "bidirectional"))
    )
    (net (code "288") (name "/IO_CR27") (class "Default")
      (node (ref "P1") (pin "33") (pinfunction "I/O_33") (pintype "bidirectional"))
    )
    (net (code "289") (name "/IO_CR28") (class "Default")
      (node (ref "P1") (pin "35") (pinfunction "I/O_35") (pintype "bidirectional"))
    )
    (net (code "290") (name "/IO_CR29") (class "Default")
      (node (ref "P1") (pin "37") (pinfunction "I/O_37") (pintype "bidirectional"))
    )
    (net (code "291") (name "/IO_CR30") (class "Default")
      (node (ref "P1") (pin "39") (pinfunction "I/O_39") (pintype "bidirectional"))
    )
    (net (code "292") (name "/IO_CR31") (class "Default")
      (node (ref "P1") (pin "43") (pinfunction "I/O_43") (pintype "bidirectional"))
    )
    (net (code "293") (name "/IO_CR32") (class "Default")
      (node (ref "P1") (pin "45") (pinfunction "I/O_45") (pintype "bidirectional"))
    )
    (net (code "296") (name "/IO_CR35") (class "Default")
      (node (ref "P1") (pin "47") (pinfunction "I/O_47") (pintype "bidirectional"))
    )
    (net (code "297") (name "/IO_CR36") (class "Default")
      (node (ref "P1") (pin "49") (pinfunction "I/O_49") (pintype "bidirectional"))
    )
    (net (code "298") (name "/IO_CR37") (class "Default")
      (node (ref "P1") (pin "53") (pinfunction "I/O_53") (pintype "bidirectional"))
    )
    (net (code "299") (name "/IO_CR38") (class "Default")
      (node (ref "P1") (pin "55") (pinfunction "I/O_55") (pintype "bidirectional"))
    )
    (net (code "300") (name "/IO_CR39") (class "Default")
      (node (ref "P1") (pin "57") (pinfunction "I/O_57") (pintype "bidirectional"))
    )
    (net (code "301") (name "/IO_CR40") (class "Default")
      (node (ref "P1") (pin "59") (pinfunction "I/O_59") (pintype "bidirectional"))
    )
    (net (code "315") (name "/ModDef_SFP0") (class "Default")
      (node (ref "U3") (pin "5") (pinfunction "IO1_5") (pintype "bidirectional"))
    )
    (net (code "316") (name "/ModDef_SFP1") (class "Default")
      (node (ref "U3") (pin "10") (pinfunction "IO5_10") (pintype "bidirectional"))
    )
    (net (code "317") (name "/ModDef_SFP2") (class "Default")
      (node (ref "U2") (pin "5") (pinfunction "IO1_5") (pintype "bidirectional"))
    )
    (net (code "318") (name "/ModDef_SFP3") (class "Default")
      (node (ref "U2") (pin "10") (pinfunction "IO5_10") (pintype "bidirectional"))
    )
    (net (code "320") (name "/PWR_EN") (class "Default") (node (ref "C12") (pin "2") (pintype "passive")))
    (net (code "321") (name "/PWR_FAIL_LED") (class "Default")
      (node (ref "R33") (pin "1") (pintype "passive"))
      (node (ref "U6") (pin "4") (pinfunction "B_4") (pintype "output"))
      (node (ref "U6") (pin "5") (pinfunction "A_5") (pintype "input"))
    )
    (net (code "322") (name "/PWR_GOOD") (class "Default")
      (node (ref "U6") (pin "3") (pinfunction "A_3") (pintype "input"))
    )
    (net (code "323") (name "/QBR_N") (class "Default")
      (node (ref "P1") (pin "12") (pinfunction "I/O_12") (pintype "bidirectional"))
      (node (ref "TP1") (pin "1") (pintype "passive"))
    )
    (net (code "324") (name "/QBR_P") (class "Default")
      (node (ref "P1") (pin "14") (pinfunction "I/O_14") (pintype "bidirectional"))
      (node (ref "TP2") (pin "1") (pintype "passive"))
    )
    (net (code "325") (name "/RateSel0_SFP0") (class "Default")
      (node (ref "U4") (pin "4") (pinfunction "IO0_4") (pintype "bidirectional"))
    )
    (net (code "326") (name "/RateSel0_SFP1") (class "Default")
      (node (ref "U4") (pin "6") (pinfunction "IO2_6") (pintype "bidirectional"))
    )
    (net (code "327") (name "/RateSel0_SFP2") (class "Default")
      (node (ref "U4") (pin "9") (pinfunction "IO4_9") (pintype "bidirectional"))
    )
    (net (code "328") (name "/RateSel0_SFP3") (class "Default")
      (node (ref "U4") (pin "11") (pinfunction "IO6_11") (pintype "bidirectional"))
    )
    (net (code "329") (name "/RateSel1_SFP0") (class "Default")
      (node (ref "U4") (pin "5") (pinfunction "IO1_5") (pintype "bidirectional"))
    )
    (net (code "330") (name "/RateSel1_SFP1") (class "Default")
      (node (ref "U4") (pin "7") (pinfunction "IO3_7") (pintype "bidirectional"))
    )
    (net (code "331") (name "/RateSel1_SFP2") (class "Default")
      (node (ref "U4") (pin "10") (pinfunction "IO5_10") (pintype "bidirectional"))
    )
    (net (code "332") (name "/RateSel1_SFP3") (class "Default")
      (node (ref "U4") (pin "12") (pinfunction "IO7_12") (pintype "bidirectional"))
    )
    (net (code "333") (name "/RxLos_SFP0") (class "Default")
      (node (ref "U3") (pin "4") (pinfunction "IO0_4") (pintype "bidirectional"))
    )
    (net (code "334") (name "/RxLos_SFP1") (class "Default")
      (node (ref "U3") (pin "9") (pinfunction "IO4_9") (pintype "bidirectional"))
    )
    (net (code "335") (name "/RxLos_SFP2") (class "Default")
      (node (ref "U2") (pin "4") (pinfunction "IO0_4") (pintype "bidirectional"))
    )
    (net (code "336") (name "/RxLos_SFP3") (class "Default")
      (node (ref "U2") (pin "9") (pinfunction "IO4_9") (pintype "bidirectional"))
    )
    (net (code "337") (name "/SDIO_SEL") (class "Default")
      (node (ref "J7") (pin "5") (pinfunction "5_5") (pintype "passive"))
    )
    (net (code "347") (name "/TX_LEMO_N") (class "Default")
      (node (ref "C9") (pin "1") (pintype "passive"))
      (node (ref "R17") (pin "2") (pintype "passive"))
      (node (ref "R18") (pin "1") (pintype "passive"))
    )
    (net (code "348") (name "/TX_LEMO_P") (class "Default")
      (node (ref "C8") (pin "1") (pintype "passive"))
      (node (ref "R13") (pin "2") (pintype "passive"))
      (node (ref "R14") (pin "1") (pintype "passive"))
    )
    (net (code "349") (name "/TxDis_SFP0") (class "Default")
      (node (ref "U3") (pin "6") (pinfunction "IO2_6") (pintype "bidirectional"))
    )
    (net (code "350") (name "/TxDis_SFP1") (class "Default")
      (node (ref "U3") (pin "11") (pinfunction "IO6_11") (pintype "bidirectional"))
    )
    (net (code "351") (name "/TxDis_SFP2") (class "Default")
      (node (ref "U2") (pin "6") (pinfunction "IO2_6") (pintype "bidirectional"))
    )
    (net (code "352") (name "/TxDis_SFP3") (class "Default")
      (node (ref "U2") (pin "11") (pinfunction "IO6_11") (pintype "bidirectional"))
    )
    (net (code "353") (name "/TxFail_SFP0") (class "Default")
      (node (ref "U3") (pin "7") (pinfunction "IO3_7") (pintype "bidirectional"))
    )
    (net (code "354") (name "/TxFail_SFP1") (class "Default")
      (node (ref "U3") (pin "12") (pinfunction "IO7_12") (pintype "bidirectional"))
    )
    (net (code "355") (name "/TxFail_SFP2") (class "Default")
      (node (ref "U2") (pin "7") (pinfunction "IO3_7") (pintype "bidirectional"))
    )
    (net (code "356") (name "/TxFail_SFP3") (class "Default")
      (node (ref "U2") (pin "12") (pinfunction "IO7_12") (pintype "bidirectional"))
    )
    (net (code "381") (name "ChasisGND") (class "Default") (node (ref "R26") (pin "2") (pintype "passive")))
    (net (code "382") (name "ChasisGND_T") (class "Default") (node (ref "R27") (pin "2") (pintype "passive")))
    (net (code "383") (name "GND") (class "Default")
      (node (ref "C1") (pin "2") (pintype "passive"))
      (node (ref "C10") (pin "2") (pintype "passive"))
      (node (ref "C11") (pin "1") (pintype "passive"))
      (node (ref "C12") (pin "1") (pintype "passive"))
      (node (ref "C13") (pin "2") (pintype "passive"))
      (node (ref "C14") (pin "2") (pintype "passive"))
      (node (ref "C15") (pin "1") (pintype "passive"))
      (node (ref "C2") (pin "2") (pintype "passive"))
      (node (ref "C3") (pin "2") (pintype "passive"))
      (node (ref "C4") (pin "2") (pintype "passive"))
      (node (ref "C7") (pin "1") (pintype "passive"))
      (node (ref "D3") (pin "2") (pinfunction "C_2") (pintype "passive"))
      (node (ref "D3") (pin "4") (pinfunction "C_4") (pintype "passive"))
      (node (ref "D3") (pin "6") (pinfunction "C_6") (pintype "passive"))
      (node (ref "D3") (pin "8") (pinfunction "C_8") (pintype "passive"))
      (node (ref "D4") (pin "1") (pinfunction "C_1") (pintype "passive"))
      (node (ref "J1") (pin "2") (pinfunction "-_2") (pintype "passive"))
      (node (ref "J10") (pin "C1") (pinfunction "C_C1") (pintype "passive"))
      (node (ref "J10") (pin "C2") (pinfunction "C_C2") (pintype "passive"))
      (node (ref "J11") (pin "2") (pintype "passive"))
      (node (ref "J12") (pin "C1") (pinfunction "C_C1") (pintype "passive"))
      (node (ref "J12") (pin "C2") (pinfunction "C_C2") (pintype "passive"))
      (node (ref "J13") (pin "3") (pintype "passive"))
      (node (ref "J13") (pin "4") (pintype "passive"))
      (node (ref "J3") (pin "2") (pinfunction "GND_2") (pintype "passive"))
      (node (ref "J4") (pin "2") (pinfunction "GND_2") (pintype "passive"))
      (node (ref "J5") (pin "2") (pinfunction "GND_2") (pintype "passive"))
      (node (ref "J6") (pin "2") (pinfunction "GND_2") (pintype "passive"))
      (node (ref "J7") (pin "1") (pinfunction "1_1") (pintype "passive"))
      (node (ref "J7") (pin "2") (pinfunction "2_2") (pintype "passive"))
      (node (ref "J7") (pin "3") (pinfunction "3_3") (pintype "passive"))
      (node (ref "J7") (pin "4") (pinfunction "4_4") (pintype "passive"))
      (node (ref "J8") (pin "2") (pinfunction "GND_2") (pintype "passive"))
      (node (ref "J9") (pin "2") (pinfunction "GND_2") (pintype "passive"))
      (node (ref "P1") (pin "1") (pinfunction "I/O_1") (pintype "bidirectional"))
      (node (ref "P1") (pin "10") (pinfunction "I/O_10") (pintype "bidirectional"))
      (node (ref "P1") (pin "13") (pinfunction "I/O_13") (pintype "bidirectional"))
      (node (ref "P1") (pin "15") (pinfunction "I/O_15") (pintype "bidirectional"))
      (node (ref "P1") (pin "16") (pinfunction "I/O_16") (pintype "bidirectional"))
      (node (ref "P1") (pin "2") (pinfunction "I/O_2") (pintype "bidirectional"))
      (node (ref "P1") (pin "21") (pinfunction "I/O_21") (pintype "bidirectional"))
      (node (ref "P1") (pin "22") (pinfunction "I/O_22") (pintype "bidirectional"))
      (node (ref "P1") (pin "31") (pinfunction "I/O_31") (pintype "bidirectional"))
      (node (ref "P1") (pin "32") (pinfunction "I/O_32") (pintype "bidirectional"))
      (node (ref "P1") (pin "41") (pinfunction "I/O_41") (pintype "bidirectional"))
      (node (ref "P1") (pin "42") (pinfunction "I/O_42") (pintype "bidirectional"))
      (node (ref "P1") (pin "51") (pinfunction "I/O_51") (pintype "bidirectional"))
      (node (ref "P1") (pin "52") (pinfunction "I/O_52") (pintype "bidirectional"))
      (node (ref "P1") (pin "61") (pinfunction "I/O_61") (pintype "bidirectional"))
      (node (ref "P1") (pin "62") (pinfunction "I/O_62") (pintype "bidirectional"))
      (node (ref "P1") (pin "63") (pinfunction "I/O_63") (pintype "bidirectional"))
      (node (ref "P1") (pin "64") (pinfunction "I/O_64") (pintype "bidirectional"))
      (node (ref "P1") (pin "7") (pinfunction "I/O_7") (pintype "bidirectional"))
      (node (ref "P1") (pin "8") (pinfunction "I/O_8") (pintype "bidirectional"))
      (node (ref "R14") (pin "2") (pintype "passive"))
      (node (ref "R18") (pin "2") (pintype "passive"))
      (node (ref "R29") (pin "2") (pintype "passive"))
      (node (ref "R30") (pin "1") (pintype "passive"))
      (node (ref "R31") (pin "2") (pintype "passive"))
      (node (ref "R32") (pin "1") (pintype "passive"))
      (node (ref "TP10") (pin "1") (pintype "passive"))
      (node (ref "TP4") (pin "1") (pintype "passive"))
      (node (ref "TP6") (pin "1") (pintype "passive"))
      (node (ref "TP8") (pin "1") (pintype "passive"))
      (node (ref "U1") (pin "10") (pinfunction "VSS_10") (pintype "power_in"))
      (node (ref "U1") (pin "3") (pinfunction "A2_3") (pintype "input"))
      (node (ref "U2") (pin "1") (pinfunction "A0_1") (pintype "input"))
      (node (ref "U2") (pin "2") (pinfunction "A1_2") (pintype "input"))
      (node (ref "U2") (pin "3") (pinfunction "A2_3") (pintype "input"))
      (node (ref "U2") (pin "8") (pinfunction "VSS_8") (pintype "power_in"))
      (node (ref "U3") (pin "2") (pinfunction "A1_2") (pintype "input"))
      (node (ref "U3") (pin "3") (pinfunction "A2_3") (pintype "input"))
      (node (ref "U3") (pin "8") (pinfunction "VSS_8") (pintype "power_in"))
      (node (ref "U4") (pin "1") (pinfunction "A0_1") (pintype "input"))
      (node (ref "U4") (pin "3") (pinfunction "A2_3") (pintype "input"))
      (node (ref "U4") (pin "8") (pinfunction "VSS_8") (pintype "power_in"))
      (node (ref "U5") (pin "1") (pinfunction "A0_1") (pintype "input"))
      (node (ref "U5") (pin "2") (pinfunction "A1_2") (pintype "input"))
      (node (ref "U5") (pin "8") (pinfunction "VSS_8") (pintype "power_in"))
      (node (ref "U6") (pin "11") (pinfunction "A_11") (pintype "input"))
      (node (ref "U6") (pin "13") (pinfunction "A_13") (pintype "input"))
      (node (ref "U6") (pin "7") (pinfunction "V-_7") (pintype "passive"))
      (node (ref "U6") (pin "9") (pinfunction "A_9") (pintype "input"))
      (node (ref "U7") (pin "2") (pinfunction "GND_2") (pintype "passive"))
    )
    (net (code "384") (name "MGND") (class "Default")
      (node (ref "J11") (pin "0") (pinfunction "S_0") (pintype "passive"))
      (node (ref "J2") (pin "5") (pinfunction "5_5") (pintype "passive"))
      (node (ref "J2") (pin "S1") (pinfunction "SHLD_S1") (pintype "passive"))
      (node (ref "J2") (pin "S2") (pinfunction "SHLD_S2") (pintype "passive"))
      (node (ref "R26") (pin "1") (pintype "passive"))
      (node (ref "R27") (pin "1") (pintype "passive"))
      (node (ref "R29") (pin "1") (pintype "passive"))
      (node (ref "R31") (pin "1") (pintype "passive"))
    )
    (net (code "385") (name "Net-(D1-C)") (class "Default")
      (node (ref "D1") (pin "2") (pinfunction "C_2") (pintype "passive"))
      (node (ref "D2") (pin "2") (pinfunction "C_2") (pintype "passive"))
      (node (ref "R8") (pin "2") (pintype "passive"))
    )
    (net (code "386") (name "Net-(D2-A)") (class "Default")
      (node (ref "D2") (pin "1") (pinfunction "A_1") (pintype "passive"))
      (node (ref "J1") (pin "1") (pinfunction "+_1") (pintype "passive"))
    )
    (net (code "387") (name "Net-(D3-A-Pad1)") (class "Default")
      (node (ref "D3") (pin "1") (pinfunction "A_1") (pintype "passive"))
      (node (ref "R25") (pin "2") (pintype "passive"))
    )
    (net (code "388") (name "Net-(D3-A-Pad3)") (class "Default")
      (node (ref "D3") (pin "3") (pinfunction "A_3") (pintype "passive"))
      (node (ref "R24") (pin "2") (pintype "passive"))
    )
    (net (code "389") (name "Net-(D3-A-Pad5)") (class "Default")
      (node (ref "D3") (pin "5") (pinfunction "A_5") (pintype "passive"))
      (node (ref "R22") (pin "2") (pintype "passive"))
    )
    (net (code "390") (name "Net-(D3-A-Pad7)") (class "Default")
      (node (ref "D3") (pin "7") (pinfunction "A_7") (pintype "passive"))
      (node (ref "R21") (pin "2") (pintype "passive"))
    )
    (net (code "391") (name "Net-(D4-A)") (class "Default")
      (node (ref "D4") (pin "2") (pinfunction "A_2") (pintype "passive"))
      (node (ref "R33") (pin "2") (pintype "passive"))
    )
    (net (code "392") (name "Net-(J3-IN)") (class "Default")
      (node (ref "J3") (pin "1") (pinfunction "IN_1") (pintype "passive"))
      (node (ref "R9") (pin "1") (pintype "passive"))
    )
    (net (code "393") (name "Net-(J4-IN)") (class "Default")
      (node (ref "J4") (pin "1") (pinfunction "IN_1") (pintype "passive"))
      (node (ref "R11") (pin "1") (pintype "passive"))
    )
    (net (code "394") (name "Net-(J5-IN)") (class "Default")
      (node (ref "J5") (pin "1") (pinfunction "IN_1") (pintype "passive"))
      (node (ref "R12") (pin "1") (pintype "passive"))
    )
    (net (code "395") (name "Net-(J6-IN)") (class "Default")
      (node (ref "J6") (pin "1") (pinfunction "IN_1") (pintype "passive"))
      (node (ref "R13") (pin "1") (pintype "passive"))
    )
    (net (code "396") (name "Net-(J8-IN)") (class "Default")
      (node (ref "J8") (pin "1") (pinfunction "IN_1") (pintype "passive"))
      (node (ref "R15") (pin "1") (pintype "passive"))
    )
    (net (code "397") (name "Net-(J9-IN)") (class "Default")
      (node (ref "J9") (pin "1") (pinfunction "IN_1") (pintype "passive"))
      (node (ref "R17") (pin "1") (pintype "passive"))
    )
    (net (code "398") (name "Net-(U1-~{INT0})") (class "Default")
      (node (ref "R3") (pin "1") (pintype "passive"))
      (node (ref "U1") (pin "11") (pinfunction "~{INT2}_11") (pintype "input"))
      (node (ref "U1") (pin "14") (pinfunction "~{INT3}_14") (pintype "input"))
      (node (ref "U1") (pin "4") (pinfunction "~{INT0}_4") (pintype "input"))
      (node (ref "U1") (pin "7") (pinfunction "~{INT1}_7") (pintype "input"))
    )
    (net (code "399") (name "Net-(U1-~{INT})") (class "Default")
      (node (ref "R1") (pin "2") (pintype "passive"))
      (node (ref "U1") (pin "17") (pinfunction "~{INT}_17") (pintype "output"))
    )
    (net (code "400") (name "Net-(U4-~{INT})") (class "Default")
      (node (ref "R2") (pin "2") (pintype "passive"))
      (node (ref "U4") (pin "13") (pinfunction "~{INT}_13") (pintype "output"))
    )
    (net (code "401") (name "Net-(U5-~{INT})") (class "Default")
      (node (ref "R10") (pin "2") (pintype "passive"))
      (node (ref "U5") (pin "13") (pinfunction "~{INT}_13") (pintype "output"))
    )
    (net (code "402") (name "Net-(U7-CT)") (class "Default")
      (node (ref "C13") (pin "1") (pintype "passive"))
      (node (ref "U7") (pin "4") (pinfunction "CT_4") (pintype "passive"))
    )
    (net (code "403") (name "Net-(U7-~{MR})") (class "Default")
      (node (ref "J11") (pin "1") (pintype "passive"))
      (node (ref "R19") (pin "2") (pintype "passive"))
      (node (ref "U7") (pin "3") (pinfunction "~{MR}_3") (pintype "passive"))
    )
    (net (code "404") (name "StripGND") (class "Default") (node (ref "R30") (pin "2") (pintype "passive")))
    (net (code "405") (name "StripGND_T") (class "Default") (node (ref "R32") (pin "2") (pintype "passive")))
    (net (code "406") (name "VBUT") (class "Default")
      (node (ref "C7") (pin "2") (pintype "passive"))
      (node (ref "R8") (pin "1") (pintype "passive"))
    )
    (net (code "407") (name "unconnected-(C5-Pad2)") (class "Default")
      (node (ref "C5") (pin "2") (pintype "passive"))
    )
    (net (code "408") (name "unconnected-(C6-Pad2)") (class "Default")
      (node (ref "C6") (pin "2") (pintype "passive"))
    )
    (net (code "409") (name "unconnected-(C8-Pad2)") (class "Default")
      (node (ref "C8") (pin "2") (pintype "passive"))
    )
    (net (code "410") (name "unconnected-(C9-Pad2)") (class "Default")
      (node (ref "C9") (pin "2") (pintype "passive"))
    )
    (net (code "411") (name "unconnected-(J2-Pad6)") (class "Default")
      (node (ref "J2") (pin "6") (pinfunction "6_6") (pintype "passive"))
    )
    (net (code "412") (name "unconnected-(J2-Pad9)") (class "Default")
      (node (ref "J2") (pin "9") (pinfunction "9_9") (pintype "passive"))
    )
    (net (code "413") (name "unconnected-(J7-Pad6)") (class "Default")
      (node (ref "J7") (pin "6") (pinfunction "6_6") (pintype "passive"))
    )
    (net (code "414") (name "unconnected-(P1-I{slash}O-Pad3)") (class "Default")
      (node (ref "P1") (pin "3") (pinfunction "I/O_3") (pintype "bidirectional"))
    )
    (net (code "415") (name "unconnected-(P1-I{slash}O-Pad4)") (class "Default")
      (node (ref "P1") (pin "4") (pinfunction "I/O_4") (pintype "bidirectional"))
    )
    (net (code "416") (name "unconnected-(P1-I{slash}O-Pad5)") (class "Default")
      (node (ref "P1") (pin "5") (pinfunction "I/O_5") (pintype "bidirectional"))
    )
    (net (code "417") (name "unconnected-(P1-I{slash}O-Pad6)") (class "Default")
      (node (ref "P1") (pin "6") (pinfunction "I/O_6") (pintype "bidirectional"))
    )
    (net (code "418") (name "unconnected-(U1-SC0-Pad6)") (class "Default")
      (node (ref "U1") (pin "6") (pinfunction "SC0_6") (pintype "output"))
    )
    (net (code "419") (name "unconnected-(U1-SC1-Pad9)") (class "Default")
      (node (ref "U1") (pin "9") (pinfunction "SC1_9") (pintype "output"))
    )
    (net (code "420") (name "unconnected-(U1-SC2-Pad13)") (class "Default")
      (node (ref "U1") (pin "13") (pinfunction "SC2_13") (pintype "output"))
    )
    (net (code "421") (name "unconnected-(U1-SC3-Pad16)") (class "Default")
      (node (ref "U1") (pin "16") (pinfunction "SC3_16") (pintype "output"))
    )
    (net (code "422") (name "unconnected-(U1-SD0-Pad5)") (class "Default")
      (node (ref "U1") (pin "5") (pinfunction "SD0_5") (pintype "bidirectional"))
    )
    (net (code "423") (name "unconnected-(U1-SD1-Pad8)") (class "Default")
      (node (ref "U1") (pin "8") (pinfunction "SD1_8") (pintype "bidirectional"))
    )
    (net (code "424") (name "unconnected-(U1-SD2-Pad12)") (class "Default")
      (node (ref "U1") (pin "12") (pinfunction "SD2_12") (pintype "bidirectional"))
    )
    (net (code "425") (name "unconnected-(U1-SD3-Pad15)") (class "Default")
      (node (ref "U1") (pin "15") (pinfunction "SD3_15") (pintype "bidirectional"))
    )
    (net (code "426") (name "unconnected-(U6D-B-Pad8)") (class "Default")
      (node (ref "U6") (pin "8") (pinfunction "B_8") (pintype "output"))
    )
    (net (code "427") (name "unconnected-(U6E-B-Pad10)") (class "Default")
      (node (ref "U6") (pin "10") (pinfunction "B_10") (pintype "output"))
    )
    (net (code "428") (name "unconnected-(U6F-B-Pad12)") (class "Default")
      (node (ref "U6") (pin "12") (pinfunction "B_12") (pintype "output"))
    )
  )
)
